# feather-v2_0.net
KiCad netlist of a schematic drawn in EAGLE
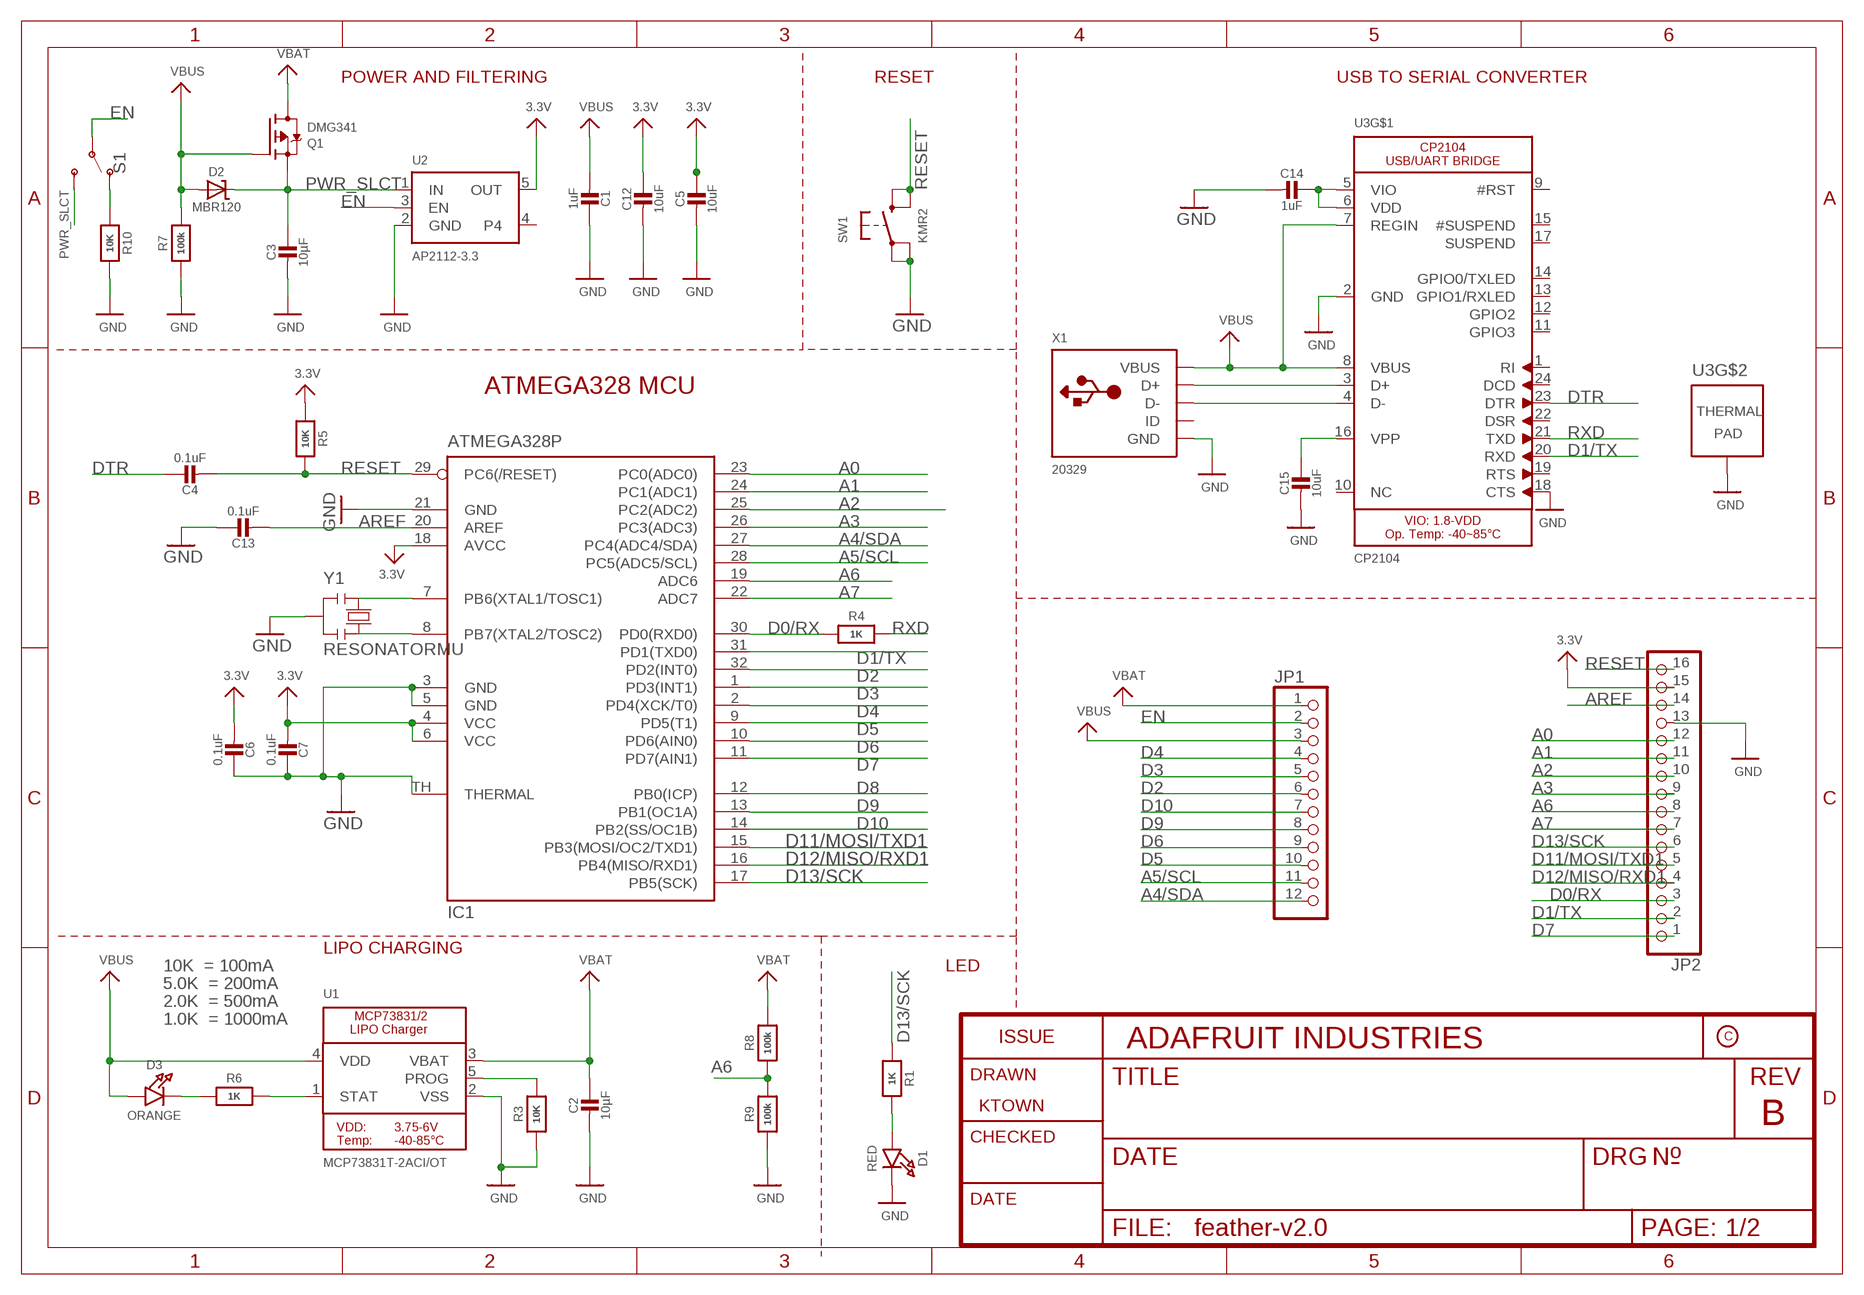
[diagram p0: schematic, sheet 1]
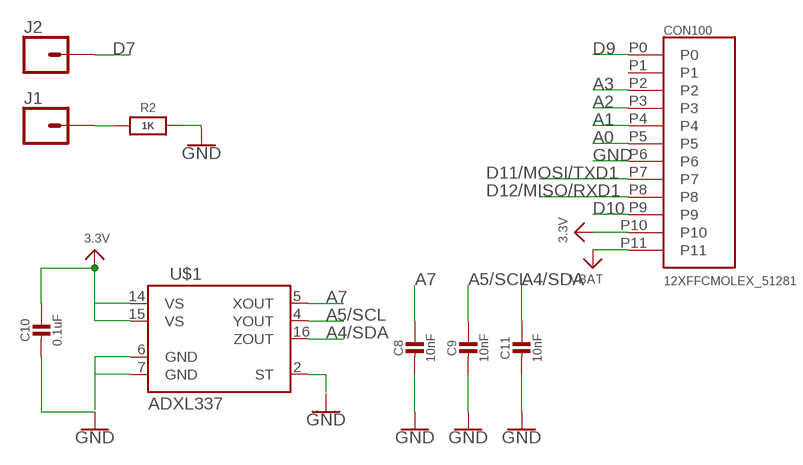
[diagram p1: schematic, sheet 2]

(export (version "E")
  (design (tool "Eeschema 10.0.6"))
  (components
    (comp (ref "C8")
      (value "10nF")
      (footprint "eagle-import:_0603MP")
      (libsource (lib "eagle-import") (part "CAP_CERAMIC_0603MP"))
    )
    (comp (ref "C9")
      (value "10nF")
      (footprint "eagle-import:_0603MP")
      (libsource (lib "eagle-import") (part "CAP_CERAMIC_0603MP"))
    )
    (comp (ref "C10")
      (value "0.1uF")
      (footprint "eagle-import:_0603MP")
      (libsource (lib "eagle-import") (part "CAP_CERAMIC_0603MP"))
    )
    (comp (ref "C11")
      (value "10nF")
      (footprint "eagle-import:_0603MP")
      (libsource (lib "eagle-import") (part "CAP_CERAMIC_0603MP"))
    )
    (comp (ref "CON100")
      (value "12XFFCMOLEX_51281")
      (footprint "eagle-import:MOLEX_51281-1294")
      (libsource (lib "eagle-import") (part "12XFFCMOLEX_51281"))
    )
    (comp (ref "J1")
      (value "CONN_01PTH_NO_SILK_YES_STOP")
      (footprint "eagle-import:1X01_NO_SILK")
      (libsource (lib "eagle-import") (part "CONN_01PTH_NO_SILK_YES_STOP"))
    )
    (comp (ref "J2")
      (value "CONN_01PTH_NO_SILK_YES_STOP")
      (footprint "eagle-import:1X01_NO_SILK")
      (libsource (lib "eagle-import") (part "CONN_01PTH_NO_SILK_YES_STOP"))
    )
    (comp (ref "R2")
      (value "1K")
      (footprint "eagle-import:_0603MP")
      (libsource (lib "eagle-import") (part "RESISTOR_0603MP"))
    )
    (comp (ref "U$1")
      (value "ADXL337")
      (footprint "eagle-import:LFCSP_LQ-16")
      (libsource (lib "eagle-import") (part "ADXL337"))
    )
    (comp (ref "C1")
      (value "1uF")
      (footprint "eagle-import:_0603MP")
      (libsource (lib "eagle-import") (part "CAP_CERAMIC_0603MP"))
    )
    (comp (ref "C2")
      (value "10µF")
      (footprint "eagle-import:_0603MP")
      (libsource (lib "eagle-import") (part "CAP_CERAMIC_0603MP"))
    )
    (comp (ref "C3")
      (value "10µF")
      (footprint "eagle-import:_0603MP")
      (libsource (lib "eagle-import") (part "CAP_CERAMIC_0603MP"))
    )
    (comp (ref "C4")
      (value "0.1uF")
      (footprint "eagle-import:_0603MP")
      (libsource (lib "eagle-import") (part "CAP_CERAMIC_0603MP"))
    )
    (comp (ref "C5")
      (value "10uF")
      (footprint "eagle-import:_0603MP")
      (libsource (lib "eagle-import") (part "CAP_CERAMIC_0603MP"))
    )
    (comp (ref "C6")
      (value "0.1uF")
      (footprint "eagle-import:_0603MP")
      (libsource (lib "eagle-import") (part "CAP_CERAMIC_0603MP"))
    )
    (comp (ref "C7")
      (value "0.1uF")
      (footprint "eagle-import:_0603MP")
      (libsource (lib "eagle-import") (part "CAP_CERAMIC_0603MP"))
    )
    (comp (ref "C12")
      (value "10uF")
      (footprint "eagle-import:_0603MP")
      (libsource (lib "eagle-import") (part "CAP_CERAMIC_0603MP"))
    )
    (comp (ref "C13")
      (value "0.1uF")
      (footprint "eagle-import:_0603MP")
      (libsource (lib "eagle-import") (part "CAP_CERAMIC_0603MP"))
    )
    (comp (ref "C14")
      (value "1uF")
      (footprint "eagle-import:_0603MP")
      (libsource (lib "eagle-import") (part "CAP_CERAMIC_0603MP"))
    )
    (comp (ref "C15")
      (value "10uF")
      (footprint "eagle-import:_0603MP")
      (libsource (lib "eagle-import") (part "CAP_CERAMIC_0603MP"))
    )
    (comp (ref "D1")
      (value "RED")
      (footprint "eagle-import:CHIPLED_0603_NOOUTLINE")
      (libsource (lib "eagle-import") (part "LED0603_NOOUTLINE"))
    )
    (comp (ref "D2")
      (value "MBR120")
      (footprint "eagle-import:SOD-323")
      (libsource (lib "eagle-import") (part "DIODE-SCHOTTKYSOD-323"))
    )
    (comp (ref "D3")
      (value "ORANGE")
      (footprint "eagle-import:CHIPLED_0603_NOOUTLINE")
      (libsource (lib "eagle-import") (part "LED0603_NOOUTLINE"))
    )
    (comp (ref "IC1")
      (value "ATMEGA328P")
      (footprint "eagle-import:MLF32-TH")
      (fields (field (name "MPN") "ATMEGA88PA-MU"))
      (libsource (lib "eagle-import") (part "MEGA8-MI"))
    )
    (comp (ref "JP1")
      (value "HEADER-1X12")
      (footprint "eagle-import:1X12_ROUND")
      (libsource (lib "eagle-import") (part "HEADER-1X12"))
    )
    (comp (ref "JP2")
      (value "HEADER-1X16ROUND")
      (footprint "eagle-import:1X16_ROUND")
      (libsource (lib "eagle-import") (part "HEADER-1X16ROUND"))
    )
    (comp (ref "Q1")
      (value "DMG341")
      (footprint "eagle-import:SOT23-R")
      (libsource (lib "eagle-import") (part "MOSFET-P"))
    )
    (comp (ref "R1")
      (value "1K")
      (footprint "eagle-import:_0603MP")
      (libsource (lib "eagle-import") (part "RESISTOR_0603MP"))
    )
    (comp (ref "R3")
      (value "10K")
      (footprint "eagle-import:_0603MP")
      (libsource (lib "eagle-import") (part "RESISTOR_0603MP"))
    )
    (comp (ref "R4")
      (value "1K")
      (footprint "eagle-import:_0603MP")
      (libsource (lib "eagle-import") (part "RESISTOR_0603MP"))
    )
    (comp (ref "R5")
      (value "10K")
      (footprint "eagle-import:_0603MP")
      (libsource (lib "eagle-import") (part "RESISTOR_0603MP"))
    )
    (comp (ref "R6")
      (value "1K")
      (footprint "eagle-import:_0603MP")
      (libsource (lib "eagle-import") (part "RESISTOR_0603MP"))
    )
    (comp (ref "R7")
      (value "100k")
      (footprint "eagle-import:_0603MP")
      (libsource (lib "eagle-import") (part "RESISTOR_0603MP"))
    )
    (comp (ref "R8")
      (value "100k")
      (footprint "eagle-import:_0603MP")
      (libsource (lib "eagle-import") (part "RESISTOR_0603MP"))
    )
    (comp (ref "R9")
      (value "100k")
      (footprint "eagle-import:_0603MP")
      (libsource (lib "eagle-import") (part "RESISTOR_0603MP"))
    )
    (comp (ref "R10")
      (value "10K")
      (footprint "eagle-import:_0603MP")
      (libsource (lib "eagle-import") (part "RESISTOR_0603MP"))
    )
    (comp (ref "S1")
      (value "SWITCH-SPDT-SMD-RIGHT-ANGLE")
      (footprint "eagle-import:SWITCH_SPST_SMD_A")
      (libsource (lib "eagle-import") (part "SWITCH-SPDT-SMD-RIGHT-ANGLE"))
    )
    (comp (ref "SW1")
      (value "KMR2")
      (footprint "eagle-import:BTN_KMR2_4.6X2.8")
      (libsource (lib "eagle-import") (part "SWITCH_TACT_SMT4.6X2.8"))
    )
    (comp (ref "U1")
      (value "MCP73831T-2ACI/OT")
      (footprint "eagle-import:SOT23-5")
      (libsource (lib "eagle-import") (part "MCP73831/2"))
    )
    (comp (ref "U2")
      (value "AP2112-3.3")
      (footprint "eagle-import:SOT23-5")
      (libsource (lib "eagle-import") (part "VREG_SOT23-5"))
    )
    (comp (ref "U3")
      (value "CP2104")
      (footprint "eagle-import:QFN24_4MM_SMSC")
      (libsource (lib "eagle-import") (part "CP2104"))
    )
    (comp (ref "X1")
      (value "20329")
      (footprint "eagle-import:4UCONN_20329_V2")
      (libsource (lib "eagle-import") (part "USB_MICRO_20329_V2"))
    )
    (comp (ref "Y1")
      (value "RESONATORMU")
      (footprint "eagle-import:RESONATOR")
      (libsource (lib "eagle-import") (part "RESONATORMU"))
    )
  )
  (nets
    (net (code "1") (name "3.3V") (class "Default")
      (node (ref "C10") (pin "1") (pinfunction "1_1") (pintype "passive"))
      (node (ref "C12") (pin "1") (pinfunction "1_1") (pintype "passive"))
      (node (ref "C5") (pin "1") (pinfunction "1_1") (pintype "passive"))
      (node (ref "C6") (pin "2") (pinfunction "2_2") (pintype "passive"))
      (node (ref "C7") (pin "2") (pinfunction "2_2") (pintype "passive"))
      (node (ref "CON100") (pin "P10") (pinfunction "P10_P10") (pintype "bidirectional"))
      (node (ref "IC1") (pin "18") (pinfunction "AVCC_18") (pintype "power_in"))
      (node (ref "IC1") (pin "4") (pinfunction "VCC_4") (pintype "power_in"))
      (node (ref "IC1") (pin "6") (pinfunction "VCC_6") (pintype "power_in"))
      (node (ref "JP2") (pin "15") (pinfunction "15_15") (pintype "passive"))
      (node (ref "R5") (pin "2") (pinfunction "2_2") (pintype "passive"))
      (node (ref "U$1") (pin "15") (pinfunction "VS_15") (pintype "bidirectional"))
      (node (ref "U2") (pin "5") (pinfunction "OUT_5") (pintype "power_in"))
    )
    (net (code "2") (name "A0") (class "Default")
      (node (ref "CON100") (pin "P5") (pinfunction "P5_P5") (pintype "bidirectional"))
      (node (ref "IC1") (pin "23") (pinfunction "PC0(ADC0)_23") (pintype "bidirectional"))
      (node (ref "JP2") (pin "12") (pinfunction "12_12") (pintype "passive"))
    )
    (net (code "3") (name "A1") (class "Default")
      (node (ref "CON100") (pin "P4") (pinfunction "P4_P4") (pintype "bidirectional"))
      (node (ref "IC1") (pin "24") (pinfunction "PC1(ADC1)_24") (pintype "bidirectional"))
      (node (ref "JP2") (pin "11") (pinfunction "11_11") (pintype "passive"))
    )
    (net (code "4") (name "A2") (class "Default")
      (node (ref "CON100") (pin "P3") (pinfunction "P3_P3") (pintype "bidirectional"))
      (node (ref "IC1") (pin "25") (pinfunction "PC2(ADC2)_25") (pintype "bidirectional"))
      (node (ref "JP2") (pin "10") (pinfunction "10_10") (pintype "passive"))
    )
    (net (code "5") (name "A3") (class "Default")
      (node (ref "CON100") (pin "P2") (pinfunction "P2_P2") (pintype "bidirectional"))
      (node (ref "IC1") (pin "26") (pinfunction "PC3(ADC3)_26") (pintype "bidirectional"))
      (node (ref "JP2") (pin "9") (pinfunction "9_9") (pintype "passive"))
    )
    (net (code "6") (name "A4{slash}SDA") (class "Default")
      (node (ref "C11") (pin "1") (pinfunction "1_1") (pintype "passive"))
      (node (ref "IC1") (pin "27") (pinfunction "PC4(ADC4/SDA)_27") (pintype "bidirectional"))
      (node (ref "JP1") (pin "12") (pinfunction "12_12") (pintype "passive"))
      (node (ref "U$1") (pin "16") (pinfunction "ZOUT_16") (pintype "bidirectional"))
    )
    (net (code "7") (name "A5{slash}SCL") (class "Default")
      (node (ref "C9") (pin "1") (pinfunction "1_1") (pintype "passive"))
      (node (ref "IC1") (pin "28") (pinfunction "PC5(ADC5/SCL)_28") (pintype "bidirectional"))
      (node (ref "JP1") (pin "11") (pinfunction "11_11") (pintype "passive"))
      (node (ref "U$1") (pin "4") (pinfunction "YOUT_4") (pintype "bidirectional"))
    )
    (net (code "8") (name "A6") (class "Default")
      (node (ref "IC1") (pin "19") (pinfunction "ADC6_19") (pintype "bidirectional"))
      (node (ref "JP2") (pin "8") (pinfunction "8_8") (pintype "passive"))
      (node (ref "R8") (pin "1") (pinfunction "1_1") (pintype "passive"))
      (node (ref "R9") (pin "2") (pinfunction "2_2") (pintype "passive"))
    )
    (net (code "9") (name "A7") (class "Default")
      (node (ref "C8") (pin "1") (pinfunction "1_1") (pintype "passive"))
      (node (ref "IC1") (pin "22") (pinfunction "ADC7_22") (pintype "bidirectional"))
      (node (ref "JP2") (pin "7") (pinfunction "7_7") (pintype "passive"))
      (node (ref "U$1") (pin "5") (pinfunction "XOUT_5") (pintype "bidirectional"))
    )
    (net (code "10") (name "AREF") (class "Default")
      (node (ref "C13") (pin "2") (pinfunction "2_2") (pintype "passive"))
      (node (ref "IC1") (pin "20") (pinfunction "AREF_20") (pintype "passive"))
      (node (ref "JP2") (pin "14") (pinfunction "14_14") (pintype "passive"))
    )
    (net (code "11") (name "D0{slash}RX") (class "Default")
      (node (ref "IC1") (pin "30") (pinfunction "PD0(RXD0)_30") (pintype "bidirectional"))
      (node (ref "JP2") (pin "3") (pinfunction "3_3") (pintype "passive"))
      (node (ref "R4") (pin "1") (pinfunction "1_1") (pintype "passive"))
    )
    (net (code "12") (name "D1{slash}TX") (class "Default")
      (node (ref "IC1") (pin "31") (pinfunction "PD1(TXD0)_31") (pintype "bidirectional"))
      (node (ref "JP2") (pin "2") (pinfunction "2_2") (pintype "passive"))
      (node (ref "U3") (pin "20") (pinfunction "RXD_20") (pintype "input"))
    )
    (net (code "13") (name "D2") (class "Default")
      (node (ref "IC1") (pin "32") (pinfunction "PD2(INT0)_32") (pintype "bidirectional"))
      (node (ref "JP1") (pin "6") (pinfunction "6_6") (pintype "passive"))
    )
    (net (code "14") (name "D3") (class "Default")
      (node (ref "IC1") (pin "1") (pinfunction "PD3(INT1)_1") (pintype "bidirectional"))
      (node (ref "JP1") (pin "5") (pinfunction "5_5") (pintype "passive"))
    )
    (net (code "15") (name "D4") (class "Default")
      (node (ref "IC1") (pin "2") (pinfunction "PD4(XCK/T0)_2") (pintype "bidirectional"))
      (node (ref "JP1") (pin "4") (pinfunction "4_4") (pintype "passive"))
    )
    (net (code "16") (name "D5") (class "Default")
      (node (ref "IC1") (pin "9") (pinfunction "PD5(T1)_9") (pintype "bidirectional"))
      (node (ref "JP1") (pin "10") (pinfunction "10_10") (pintype "passive"))
    )
    (net (code "17") (name "D6") (class "Default")
      (node (ref "IC1") (pin "10") (pinfunction "PD6(AIN0)_10") (pintype "bidirectional"))
      (node (ref "JP1") (pin "9") (pinfunction "9_9") (pintype "passive"))
    )
    (net (code "18") (name "D7") (class "Default")
      (node (ref "IC1") (pin "11") (pinfunction "PD7(AIN1)_11") (pintype "bidirectional"))
      (node (ref "J2") (pin "1") (pinfunction "1_1") (pintype "passive"))
      (node (ref "JP2") (pin "1") (pinfunction "1_1") (pintype "passive"))
    )
    (net (code "19") (name "D8") (class "Default")
      (node (ref "IC1") (pin "12") (pinfunction "PB0(ICP)_12") (pintype "bidirectional"))
    )
    (net (code "20") (name "D9") (class "Default")
      (node (ref "CON100") (pin "P0") (pinfunction "P0_P0") (pintype "bidirectional"))
      (node (ref "IC1") (pin "13") (pinfunction "PB1(OC1A)_13") (pintype "bidirectional"))
      (node (ref "JP1") (pin "8") (pinfunction "8_8") (pintype "passive"))
    )
    (net (code "21") (name "D10") (class "Default")
      (node (ref "CON100") (pin "P9") (pinfunction "P9_P9") (pintype "bidirectional"))
      (node (ref "IC1") (pin "14") (pinfunction "PB2(SS/OC1B)_14") (pintype "bidirectional"))
      (node (ref "JP1") (pin "7") (pinfunction "7_7") (pintype "passive"))
    )
    (net (code "22") (name "D11{slash}MOSI{slash}TXD1") (class "Default")
      (node (ref "CON100") (pin "P7") (pinfunction "P7_P7") (pintype "bidirectional"))
      (node (ref "IC1") (pin "15") (pinfunction "PB3(MOSI/OC2/TXD1)_15") (pintype "bidirectional"))
      (node (ref "JP2") (pin "5") (pinfunction "5_5") (pintype "passive"))
    )
    (net (code "23") (name "D12{slash}MISO{slash}RXD1") (class "Default")
      (node (ref "CON100") (pin "P8") (pinfunction "P8_P8") (pintype "bidirectional"))
      (node (ref "IC1") (pin "16") (pinfunction "PB4(MISO/RXD1)_16") (pintype "bidirectional"))
      (node (ref "JP2") (pin "4") (pinfunction "4_4") (pintype "passive"))
    )
    (net (code "24") (name "D13{slash}SCK") (class "Default")
      (node (ref "IC1") (pin "17") (pinfunction "PB5(SCK)_17") (pintype "bidirectional"))
      (node (ref "JP2") (pin "6") (pinfunction "6_6") (pintype "passive"))
      (node (ref "R1") (pin "1") (pinfunction "1_1") (pintype "passive"))
    )
    (net (code "25") (name "DTR") (class "Default")
      (node (ref "C4") (pin "1") (pinfunction "1_1") (pintype "passive"))
      (node (ref "U3") (pin "23") (pinfunction "DTR_23") (pintype "output"))
    )
    (net (code "26") (name "EN") (class "Default")
      (node (ref "JP1") (pin "2") (pinfunction "2_2") (pintype "passive"))
      (node (ref "S1") (pin "2") (pinfunction "P_2") (pintype "passive"))
      (node (ref "U2") (pin "3") (pinfunction "EN_3") (pintype "input"))
    )
    (net (code "27") (name "GND") (class "Default")
      (node (ref "C1") (pin "1") (pinfunction "1_1") (pintype "passive"))
      (node (ref "C10") (pin "2") (pinfunction "2_2") (pintype "passive"))
      (node (ref "C11") (pin "2") (pinfunction "2_2") (pintype "passive"))
      (node (ref "C12") (pin "2") (pinfunction "2_2") (pintype "passive"))
      (node (ref "C13") (pin "1") (pinfunction "1_1") (pintype "passive"))
      (node (ref "C14") (pin "2") (pinfunction "2_2") (pintype "passive"))
      (node (ref "C15") (pin "2") (pinfunction "2_2") (pintype "passive"))
      (node (ref "C2") (pin "2") (pinfunction "2_2") (pintype "passive"))
      (node (ref "C3") (pin "2") (pinfunction "2_2") (pintype "passive"))
      (node (ref "C5") (pin "2") (pinfunction "2_2") (pintype "passive"))
      (node (ref "C6") (pin "1") (pinfunction "1_1") (pintype "passive"))
      (node (ref "C7") (pin "1") (pinfunction "1_1") (pintype "passive"))
      (node (ref "C8") (pin "2") (pinfunction "2_2") (pintype "passive"))
      (node (ref "C9") (pin "2") (pinfunction "2_2") (pintype "passive"))
      (node (ref "CON100") (pin "P6") (pinfunction "P6_P6") (pintype "bidirectional"))
      (node (ref "D1") (pin "C") (pinfunction "C_C") (pintype "passive"))
      (node (ref "IC1") (pin "21") (pinfunction "GND_21") (pintype "power_in"))
      (node (ref "IC1") (pin "3") (pinfunction "GND_3") (pintype "power_in"))
      (node (ref "IC1") (pin "5") (pinfunction "GND_5") (pintype "power_in"))
      (node (ref "IC1") (pin "TH") (pinfunction "THERMAL_TH") (pintype "passive"))
      (node (ref "JP2") (pin "13") (pinfunction "13_13") (pintype "passive"))
      (node (ref "R10") (pin "1") (pinfunction "1_1") (pintype "passive"))
      (node (ref "R2") (pin "2") (pinfunction "2_2") (pintype "passive"))
      (node (ref "R3") (pin "1") (pinfunction "1_1") (pintype "passive"))
      (node (ref "R7") (pin "1") (pinfunction "1_1") (pintype "passive"))
      (node (ref "R9") (pin "1") (pinfunction "1_1") (pintype "passive"))
      (node (ref "SW1") (pin "A") (pinfunction "P_A") (pintype "passive"))
      (node (ref "SW1") (pin "A'") (pinfunction "P1_A'") (pintype "passive"))
      (node (ref "U1") (pin "2") (pinfunction "VSS_2") (pintype "power_in"))
      (node (ref "U2") (pin "2") (pinfunction "GND_2") (pintype "power_in"))
      (node (ref "U3") (pin "18") (pinfunction "CTS_18") (pintype "input"))
      (node (ref "U3") (pin "2") (pinfunction "GND_2") (pintype "power_in"))
      (node (ref "U3") (pin "THERM") (pinfunction "TP_THERM") (pintype "power_in"))
      (node (ref "X1") (pin "BASE@1") (pinfunction "GND_BASE@1") (pintype "power_in"))
      (node (ref "X1") (pin "BASE@2") (pinfunction "GND_BASE@2") (pintype "power_in"))
      (node (ref "X1") (pin "GND") (pinfunction "GND_GND") (pintype "power_in"))
      (node (ref "X1") (pin "SPRT@1") (pinfunction "GND_SPRT@1") (pintype "power_in"))
      (node (ref "X1") (pin "SPRT@2") (pinfunction "GND_SPRT@2") (pintype "power_in"))
      (node (ref "X1") (pin "SPRT@3") (pinfunction "GND_SPRT@3") (pintype "power_in"))
      (node (ref "X1") (pin "SPRT@4") (pinfunction "GND_SPRT@4") (pintype "power_in"))
      (node (ref "Y1") (pin "2") (pinfunction "2_2") (pintype "passive"))
    )
    (net (code "28") (name "Net-(D1-PadA)") (class "Default")
      (node (ref "D1") (pin "A") (pinfunction "A_A") (pintype "passive"))
      (node (ref "R1") (pin "2") (pinfunction "2_2") (pintype "passive"))
    )
    (net (code "29") (name "Net-(D3-PadC)") (class "Default")
      (node (ref "D3") (pin "C") (pinfunction "C_C") (pintype "passive"))
      (node (ref "R6") (pin "1") (pinfunction "1_1") (pintype "passive"))
    )
    (net (code "30") (name "Net-(IC1-PB6(XTAL1{slash}TOSC1))") (class "Default")
      (node (ref "IC1") (pin "7") (pinfunction "PB6(XTAL1/TOSC1)_7") (pintype "bidirectional"))
      (node (ref "Y1") (pin "1") (pinfunction "1_1") (pintype "passive"))
    )
    (net (code "31") (name "Net-(IC1-PB7(XTAL2{slash}TOSC2))") (class "Default")
      (node (ref "IC1") (pin "8") (pinfunction "PB7(XTAL2/TOSC2)_8") (pintype "bidirectional"))
      (node (ref "Y1") (pin "3") (pinfunction "3_3") (pintype "passive"))
    )
    (net (code "32") (name "Net-(J1-Pad1)") (class "Default")
      (node (ref "J1") (pin "1") (pinfunction "1_1") (pintype "passive"))
      (node (ref "R2") (pin "1") (pinfunction "1_1") (pintype "passive"))
    )
    (net (code "33") (name "Net-(S1-O)") (class "Default")
      (node (ref "R10") (pin "2") (pinfunction "2_2") (pintype "passive"))
      (node (ref "S1") (pin "1") (pinfunction "O_1") (pintype "passive"))
    )
    (net (code "34") (name "Net-(U1-PROG)") (class "Default")
      (node (ref "R3") (pin "2") (pinfunction "2_2") (pintype "passive"))
      (node (ref "U1") (pin "5") (pinfunction "PROG_5") (pintype "input"))
    )
    (net (code "35") (name "Net-(U1-STAT)") (class "Default")
      (node (ref "R6") (pin "2") (pinfunction "2_2") (pintype "passive"))
      (node (ref "U1") (pin "1") (pinfunction "STAT_1") (pintype "output"))
    )
    (net (code "36") (name "Net-(U3A-D+)") (class "Default")
      (node (ref "U3") (pin "3") (pinfunction "D+_3") (pintype "bidirectional"))
      (node (ref "X1") (pin "D+") (pinfunction "D+_D+") (pintype "bidirectional"))
    )
    (net (code "37") (name "Net-(U3A-D-)") (class "Default")
      (node (ref "U3") (pin "4") (pinfunction "D-_4") (pintype "bidirectional"))
      (node (ref "X1") (pin "D-") (pinfunction "D-_D-") (pintype "bidirectional"))
    )
    (net (code "38") (name "Net-(U3A-VDD)") (class "Default")
      (node (ref "C14") (pin "1") (pinfunction "1_1") (pintype "passive"))
      (node (ref "U3") (pin "5") (pinfunction "VIO_5") (pintype "power_in"))
      (node (ref "U3") (pin "6") (pinfunction "VDD_6") (pintype "power_in"))
    )
    (net (code "39") (name "Net-(U3A-VPP)") (class "Default")
      (node (ref "C15") (pin "1") (pinfunction "1_1") (pintype "passive"))
      (node (ref "U3") (pin "16") (pinfunction "VPP_16") (pintype "bidirectional"))
    )
    (net (code "40") (name "PWR_SLCT") (class "Default")
      (node (ref "C3") (pin "1") (pinfunction "1_1") (pintype "passive"))
      (node (ref "D2") (pin "C") (pinfunction "C_C") (pintype "passive"))
      (node (ref "Q1") (pin "2") (pinfunction "S_2") (pintype "passive"))
      (node (ref "S1") (pin "3") (pinfunction "S_3") (pintype "passive"))
      (node (ref "U2") (pin "1") (pinfunction "IN_1") (pintype "power_in"))
    )
    (net (code "41") (name "RESET") (class "Default")
      (node (ref "C4") (pin "2") (pinfunction "2_2") (pintype "passive"))
      (node (ref "IC1") (pin "29") (pinfunction "PC6(/RESET)_29") (pintype "bidirectional"))
      (node (ref "JP2") (pin "16") (pinfunction "16_16") (pintype "passive"))
      (node (ref "R5") (pin "1") (pinfunction "1_1") (pintype "passive"))
      (node (ref "SW1") (pin "B") (pinfunction "S_B") (pintype "passive"))
      (node (ref "SW1") (pin "B'") (pinfunction "S1_B'") (pintype "passive"))
    )
    (net (code "42") (name "RXD") (class "Default")
      (node (ref "R4") (pin "2") (pinfunction "2_2") (pintype "passive"))
      (node (ref "U3") (pin "21") (pinfunction "TXD_21") (pintype "output"))
    )
    (net (code "43") (name "VBAT") (class "Default")
      (node (ref "C2") (pin "1") (pinfunction "1_1") (pintype "passive"))
      (node (ref "CON100") (pin "P11") (pinfunction "P11_P11") (pintype "bidirectional"))
      (node (ref "JP1") (pin "1") (pinfunction "1_1") (pintype "passive"))
      (node (ref "Q1") (pin "3") (pinfunction "D_3") (pintype "passive"))
      (node (ref "R8") (pin "2") (pinfunction "2_2") (pintype "passive"))
      (node (ref "U1") (pin "3") (pinfunction "VBAT_3") (pintype "power_in"))
    )
    (net (code "44") (name "VBUS") (class "Default")
      (node (ref "C1") (pin "2") (pinfunction "2_2") (pintype "passive"))
      (node (ref "D2") (pin "A") (pinfunction "A_A") (pintype "passive"))
      (node (ref "D3") (pin "A") (pinfunction "A_A") (pintype "passive"))
      (node (ref "JP1") (pin "3") (pinfunction "3_3") (pintype "passive"))
      (node (ref "Q1") (pin "1") (pinfunction "G_1") (pintype "passive"))
      (node (ref "R7") (pin "2") (pinfunction "2_2") (pintype "passive"))
      (node (ref "U1") (pin "4") (pinfunction "VDD_4") (pintype "power_in"))
      (node (ref "U3") (pin "7") (pinfunction "REGIN_7") (pintype "power_in"))
      (node (ref "U3") (pin "8") (pinfunction "VBUS_8") (pintype "power_in"))
      (node (ref "X1") (pin "VBUS") (pinfunction "VBUS_VBUS") (pintype "power_in"))
    )
    (net (code "45") (name "unconnected-(CON100-PadP1)") (class "Default")
      (node (ref "CON100") (pin "P1") (pinfunction "P1_P1") (pintype "bidirectional"))
    )
    (net (code "46") (name "unconnected-(U$1-GND-Pad6)") (class "Default")
      (node (ref "U$1") (pin "6") (pinfunction "GND_6") (pintype "bidirectional"))
    )
    (net (code "47") (name "unconnected-(U$1-GND-Pad7)") (class "Default")
      (node (ref "U$1") (pin "7") (pinfunction "GND_7") (pintype "bidirectional"))
    )
    (net (code "48") (name "unconnected-(U$1-ST-Pad2)") (class "Default")
      (node (ref "U$1") (pin "2") (pinfunction "ST_2") (pintype "bidirectional"))
    )
    (net (code "49") (name "unconnected-(U$1-VS-Pad14)") (class "Default")
      (node (ref "U$1") (pin "14") (pinfunction "VS_14") (pintype "bidirectional"))
    )
    (net (code "50") (name "unconnected-(U2-P4-Pad4)") (class "Default")
      (node (ref "U2") (pin "4") (pinfunction "P4_4") (pintype "bidirectional"))
    )
    (net (code "51") (name "unconnected-(U3A-#RST-Pad9)") (class "Default")
      (node (ref "U3") (pin "9") (pinfunction "#RST_9") (pintype "bidirectional"))
    )
    (net (code "52") (name "unconnected-(U3A-#SUSPEND-Pad15)") (class "Default")
      (node (ref "U3") (pin "15") (pinfunction "#SUSPEND_15") (pintype "output"))
    )
    (net (code "53") (name "unconnected-(U3A-DCD-Pad24)") (class "Default")
      (node (ref "U3") (pin "24") (pinfunction "DCD_24") (pintype "input"))
    )
    (net (code "54") (name "unconnected-(U3A-DSR-Pad22)") (class "Default")
      (node (ref "U3") (pin "22") (pinfunction "DSR_22") (pintype "input"))
    )
    (net (code "55") (name "unconnected-(U3A-GPIO0{slash}TXLED-Pad14)") (class "Default")
      (node (ref "U3") (pin "14") (pinfunction "GPIO0/TXLED_14") (pintype "bidirectional"))
    )
    (net (code "56") (name "unconnected-(U3A-GPIO1{slash}RXLED-Pad13)") (class "Default")
      (node (ref "U3") (pin "13") (pinfunction "GPIO1/RXLED_13") (pintype "bidirectional"))
    )
    (net (code "57") (name "unconnected-(U3A-GPIO2-Pad12)") (class "Default")
      (node (ref "U3") (pin "12") (pinfunction "GPIO2_12") (pintype "bidirectional"))
    )
    (net (code "58") (name "unconnected-(U3A-GPIO3-Pad11)") (class "Default")
      (node (ref "U3") (pin "11") (pinfunction "GPIO3_11") (pintype "bidirectional"))
    )
    (net (code "59") (name "unconnected-(U3A-NC-Pad10)") (class "Default")
      (node (ref "U3") (pin "10") (pinfunction "NC_10") (pintype "no_connect"))
    )
    (net (code "60") (name "unconnected-(U3A-RI-Pad1)") (class "Default")
      (node (ref "U3") (pin "1") (pinfunction "RI_1") (pintype "input"))
    )
    (net (code "61") (name "unconnected-(U3A-RTS-Pad19)") (class "Default")
      (node (ref "U3") (pin "19") (pinfunction "RTS_19") (pintype "output"))
    )
    (net (code "62") (name "unconnected-(U3A-SUSPEND-Pad17)") (class "Default")
      (node (ref "U3") (pin "17") (pinfunction "SUSPEND_17") (pintype "output"))
    )
    (net (code "63") (name "unconnected-(X1-PadID)") (class "Default")
      (node (ref "X1") (pin "ID") (pinfunction "ID_ID") (pintype "bidirectional"))
    )
  )
)
